# Hi_Tension_VGA_Modulator.net
KiCad netlist of a schematic drawn in EAGLE
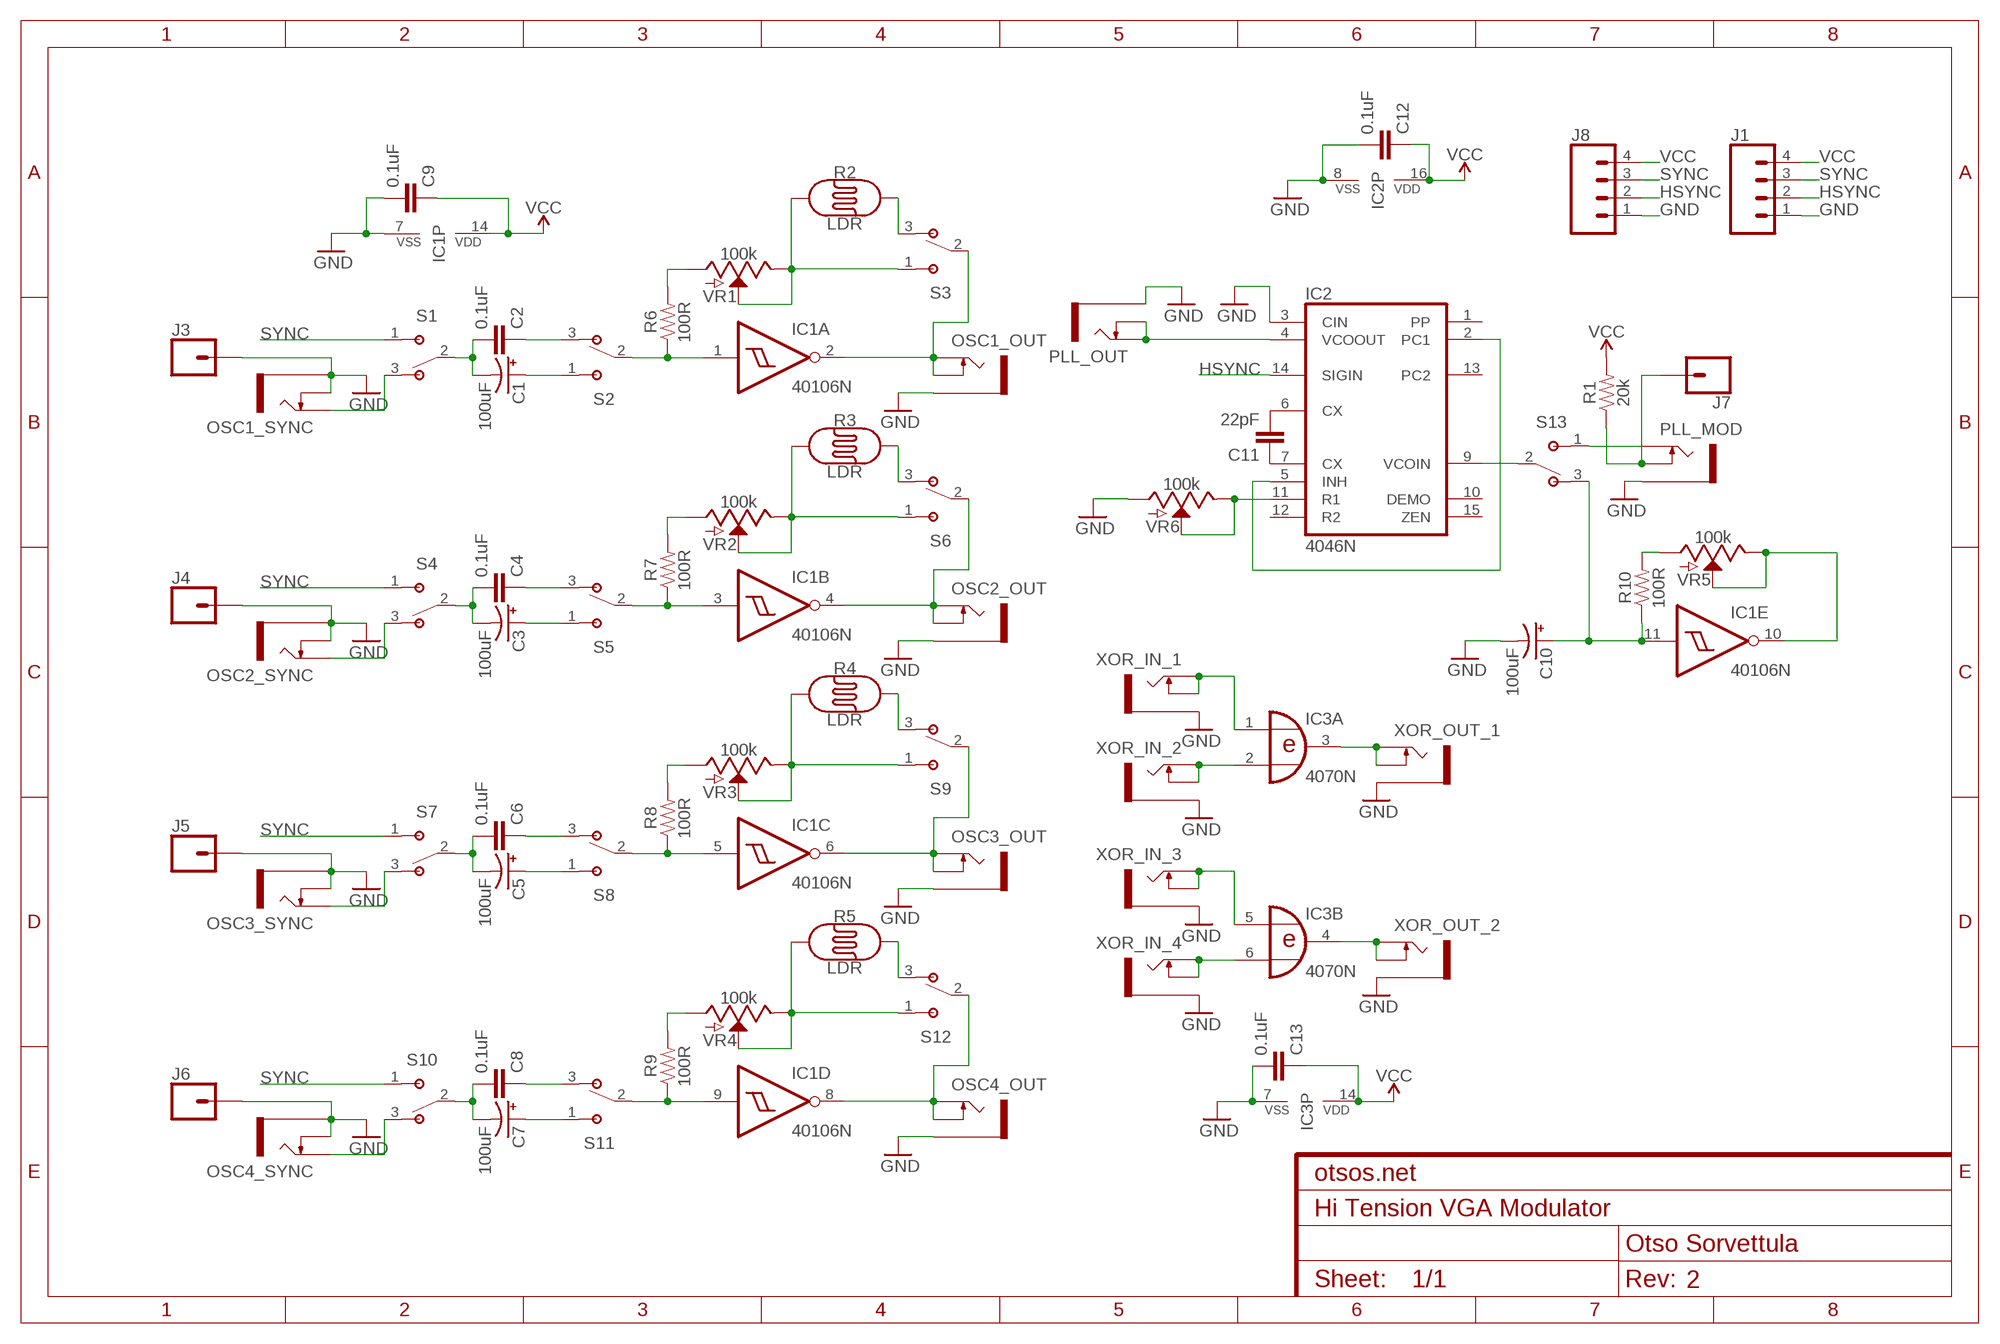
[diagram p0: schematic, sheet 1]

(export (version "E")
  (design (tool "Eeschema 10.0.6"))
  (components
    (comp (ref "C1")
      (value "100uF")
      (footprint "eagle-import:CPOL-RADIAL-2.5MM-6.5MM")
      (libsource (lib "eagle-import") (part "100UF-POLAR-RADIAL-2.5MM-25V-20%"))
    )
    (comp (ref "C2")
      (value "0.1uF")
      (footprint "eagle-import:C025-025X050")
      (libsource (lib "eagle-import") (part "C-EU025-025X050"))
    )
    (comp (ref "C3")
      (value "100uF")
      (footprint "eagle-import:CPOL-RADIAL-2.5MM-6.5MM")
      (libsource (lib "eagle-import") (part "100UF-POLAR-RADIAL-2.5MM-25V-20%"))
    )
    (comp (ref "C4")
      (value "0.1uF")
      (footprint "eagle-import:C025-025X050")
      (libsource (lib "eagle-import") (part "C-EU025-025X050"))
    )
    (comp (ref "C5")
      (value "100uF")
      (footprint "eagle-import:CPOL-RADIAL-2.5MM-6.5MM")
      (libsource (lib "eagle-import") (part "100UF-POLAR-RADIAL-2.5MM-25V-20%"))
    )
    (comp (ref "C6")
      (value "0.1uF")
      (footprint "eagle-import:C025-025X050")
      (libsource (lib "eagle-import") (part "C-EU025-025X050"))
    )
    (comp (ref "C7")
      (value "100uF")
      (footprint "eagle-import:CPOL-RADIAL-2.5MM-6.5MM")
      (libsource (lib "eagle-import") (part "100UF-POLAR-RADIAL-2.5MM-25V-20%"))
    )
    (comp (ref "C8")
      (value "0.1uF")
      (footprint "eagle-import:C025-025X050")
      (libsource (lib "eagle-import") (part "C-EU025-025X050"))
    )
    (comp (ref "C9")
      (value "0.1uF")
      (footprint "eagle-import:C025-025X050")
      (libsource (lib "eagle-import") (part "C-EU025-025X050"))
    )
    (comp (ref "C10")
      (value "100uF")
      (footprint "eagle-import:CPOL-RADIAL-2.5MM-6.5MM")
      (libsource (lib "eagle-import") (part "100UF-POLAR-RADIAL-2.5MM-25V-20%"))
    )
    (comp (ref "C11")
      (value "22pF")
      (footprint "eagle-import:CAP-PTH-2.54")
      (libsource (lib "eagle-import") (part "22PF-PTH-2.54MM-200V-5%"))
    )
    (comp (ref "C12")
      (value "0.1uF")
      (footprint "eagle-import:C025-025X050")
      (libsource (lib "eagle-import") (part "C-EU025-025X050"))
    )
    (comp (ref "C13")
      (value "0.1uF")
      (footprint "eagle-import:C025-025X050")
      (libsource (lib "eagle-import") (part "C-EU025-025X050"))
    )
    (comp (ref "IC1")
      (value "40106N")
      (footprint "eagle-import:DIL14")
      (libsource (lib "eagle-import") (part "40106N"))
    )
    (comp (ref "IC2")
      (value "4046N")
      (footprint "eagle-import:DIL16")
      (libsource (lib "eagle-import") (part "4046N"))
    )
    (comp (ref "IC3")
      (value "4070N")
      (footprint "eagle-import:DIL14")
      (libsource (lib "eagle-import") (part "4070N"))
    )
    (comp (ref "J1")
      (value "CONN_04")
      (footprint "eagle-import:1X04")
      (libsource (lib "eagle-import") (part "CONN_04"))
    )
    (comp (ref "J3")
      (value "CONN_01PTH_NO_SILK_YES_STOP")
      (footprint "eagle-import:1X01_NO_SILK")
      (libsource (lib "eagle-import") (part "CONN_01PTH_NO_SILK_YES_STOP"))
    )
    (comp (ref "J4")
      (value "CONN_01PTH_NO_SILK_YES_STOP")
      (footprint "eagle-import:1X01_NO_SILK")
      (libsource (lib "eagle-import") (part "CONN_01PTH_NO_SILK_YES_STOP"))
    )
    (comp (ref "J5")
      (value "CONN_01PTH_NO_SILK_YES_STOP")
      (footprint "eagle-import:1X01_NO_SILK")
      (libsource (lib "eagle-import") (part "CONN_01PTH_NO_SILK_YES_STOP"))
    )
    (comp (ref "J6")
      (value "CONN_01PTH_NO_SILK_YES_STOP")
      (footprint "eagle-import:1X01_NO_SILK")
      (libsource (lib "eagle-import") (part "CONN_01PTH_NO_SILK_YES_STOP"))
    )
    (comp (ref "J7")
      (value "CONN_01PTH_NO_SILK_YES_STOP")
      (footprint "eagle-import:1X01_NO_SILK")
      (libsource (lib "eagle-import") (part "CONN_01PTH_NO_SILK_YES_STOP"))
    )
    (comp (ref "J8")
      (value "CONN_04")
      (footprint "eagle-import:1X04")
      (libsource (lib "eagle-import") (part "CONN_04"))
    )
    (comp (ref "OSC1_OUT")
      (value "THONKICONNNEW")
      (footprint "eagle-import:WQP-PJ301M-12_JACK")
      (libsource (lib "eagle-import") (part "THONKICONNNEW"))
    )
    (comp (ref "OSC1_SYNC")
      (value "THONKICONNNEW")
      (footprint "eagle-import:WQP-PJ301M-12_JACK")
      (libsource (lib "eagle-import") (part "THONKICONNNEW"))
    )
    (comp (ref "OSC2_OUT")
      (value "THONKICONNNEW")
      (footprint "eagle-import:WQP-PJ301M-12_JACK")
      (libsource (lib "eagle-import") (part "THONKICONNNEW"))
    )
    (comp (ref "OSC2_SYNC")
      (value "THONKICONNNEW")
      (footprint "eagle-import:WQP-PJ301M-12_JACK")
      (libsource (lib "eagle-import") (part "THONKICONNNEW"))
    )
    (comp (ref "OSC3_OUT")
      (value "THONKICONNNEW")
      (footprint "eagle-import:WQP-PJ301M-12_JACK")
      (libsource (lib "eagle-import") (part "THONKICONNNEW"))
    )
    (comp (ref "OSC3_SYNC")
      (value "THONKICONNNEW")
      (footprint "eagle-import:WQP-PJ301M-12_JACK")
      (libsource (lib "eagle-import") (part "THONKICONNNEW"))
    )
    (comp (ref "OSC4_OUT")
      (value "THONKICONNNEW")
      (footprint "eagle-import:WQP-PJ301M-12_JACK")
      (libsource (lib "eagle-import") (part "THONKICONNNEW"))
    )
    (comp (ref "OSC4_SYNC")
      (value "THONKICONNNEW")
      (footprint "eagle-import:WQP-PJ301M-12_JACK")
      (libsource (lib "eagle-import") (part "THONKICONNNEW"))
    )
    (comp (ref "PLL_MOD")
      (value "THONKICONNNEW")
      (footprint "eagle-import:WQP-PJ301M-12_JACK")
      (libsource (lib "eagle-import") (part "THONKICONNNEW"))
    )
    (comp (ref "PLL_OUT")
      (value "THONKICONNNEW")
      (footprint "eagle-import:WQP-PJ301M-12_JACK")
      (libsource (lib "eagle-import") (part "THONKICONNNEW"))
    )
    (comp (ref "R1")
      (value "20k")
      (footprint "eagle-import:AXIAL-0.3")
      (libsource (lib "eagle-import") (part "1KOHM-HORIZ-1/4W-1%"))
    )
    (comp (ref "R2")
      (value "LDR")
      (footprint "eagle-import:PHOTOCELL")
      (libsource (lib "eagle-import") (part "PHOTOCELLPTH"))
    )
    (comp (ref "R3")
      (value "LDR")
      (footprint "eagle-import:PHOTOCELL")
      (libsource (lib "eagle-import") (part "PHOTOCELLPTH"))
    )
    (comp (ref "R4")
      (value "LDR")
      (footprint "eagle-import:PHOTOCELL")
      (libsource (lib "eagle-import") (part "PHOTOCELLPTH"))
    )
    (comp (ref "R5")
      (value "LDR")
      (footprint "eagle-import:PHOTOCELL")
      (libsource (lib "eagle-import") (part "PHOTOCELLPTH"))
    )
    (comp (ref "R6")
      (value "100R")
      (footprint "eagle-import:AXIAL-0.3")
      (libsource (lib "eagle-import") (part "1KOHM-HORIZ-1/4W-1%"))
    )
    (comp (ref "R7")
      (value "100R")
      (footprint "eagle-import:AXIAL-0.3")
      (libsource (lib "eagle-import") (part "1KOHM-HORIZ-1/4W-1%"))
    )
    (comp (ref "R8")
      (value "100R")
      (footprint "eagle-import:AXIAL-0.3")
      (libsource (lib "eagle-import") (part "1KOHM-HORIZ-1/4W-1%"))
    )
    (comp (ref "R9")
      (value "100R")
      (footprint "eagle-import:AXIAL-0.3")
      (libsource (lib "eagle-import") (part "1KOHM-HORIZ-1/4W-1%"))
    )
    (comp (ref "R10")
      (value "100R")
      (footprint "eagle-import:AXIAL-0.3")
      (libsource (lib "eagle-import") (part "1KOHM-HORIZ-1/4W-1%"))
    )
    (comp (ref "S1")
      (value "OS102011MS2QN1")
      (footprint "eagle-import:SW_OS102011MS2QN1")
      (fields (field (name "MF") "C&K"))
      (libsource (lib "eagle-import") (part "OS102011MS2QN1"))
    )
    (comp (ref "S2")
      (value "OS102011MS2QN1")
      (footprint "eagle-import:SW_OS102011MS2QN1")
      (fields (field (name "MF") "C&K"))
      (libsource (lib "eagle-import") (part "OS102011MS2QN1"))
    )
    (comp (ref "S3")
      (value "OS102011MS2QN1")
      (footprint "eagle-import:SW_OS102011MS2QN1")
      (fields (field (name "MF") "C&K"))
      (libsource (lib "eagle-import") (part "OS102011MS2QN1"))
    )
    (comp (ref "S4")
      (value "OS102011MS2QN1")
      (footprint "eagle-import:SW_OS102011MS2QN1")
      (fields (field (name "MF") "C&K"))
      (libsource (lib "eagle-import") (part "OS102011MS2QN1"))
    )
    (comp (ref "S5")
      (value "OS102011MS2QN1")
      (footprint "eagle-import:SW_OS102011MS2QN1")
      (fields (field (name "MF") "C&K"))
      (libsource (lib "eagle-import") (part "OS102011MS2QN1"))
    )
    (comp (ref "S6")
      (value "OS102011MS2QN1")
      (footprint "eagle-import:SW_OS102011MS2QN1")
      (fields (field (name "MF") "C&K"))
      (libsource (lib "eagle-import") (part "OS102011MS2QN1"))
    )
    (comp (ref "S7")
      (value "OS102011MS2QN1")
      (footprint "eagle-import:SW_OS102011MS2QN1")
      (fields (field (name "MF") "C&K"))
      (libsource (lib "eagle-import") (part "OS102011MS2QN1"))
    )
    (comp (ref "S8")
      (value "OS102011MS2QN1")
      (footprint "eagle-import:SW_OS102011MS2QN1")
      (fields (field (name "MF") "C&K"))
      (libsource (lib "eagle-import") (part "OS102011MS2QN1"))
    )
    (comp (ref "S9")
      (value "OS102011MS2QN1")
      (footprint "eagle-import:SW_OS102011MS2QN1")
      (fields (field (name "MF") "C&K"))
      (libsource (lib "eagle-import") (part "OS102011MS2QN1"))
    )
    (comp (ref "S10")
      (value "OS102011MS2QN1")
      (footprint "eagle-import:SW_OS102011MS2QN1")
      (fields (field (name "MF") "C&K"))
      (libsource (lib "eagle-import") (part "OS102011MS2QN1"))
    )
    (comp (ref "S11")
      (value "OS102011MS2QN1")
      (footprint "eagle-import:SW_OS102011MS2QN1")
      (fields (field (name "MF") "C&K"))
      (libsource (lib "eagle-import") (part "OS102011MS2QN1"))
    )
    (comp (ref "S12")
      (value "OS102011MS2QN1")
      (footprint "eagle-import:SW_OS102011MS2QN1")
      (fields (field (name "MF") "C&K"))
      (libsource (lib "eagle-import") (part "OS102011MS2QN1"))
    )
    (comp (ref "S13")
      (value "OS102011MS2QN1")
      (footprint "eagle-import:SW_OS102011MS2QN1")
      (fields (field (name "MF") "C&K"))
      (libsource (lib "eagle-import") (part "OS102011MS2QN1"))
    )
    (comp (ref "VR1")
      (value "100k")
      (footprint "eagle-import:POT-PTH-ALPS")
      (libsource (lib "eagle-import") (part "POTENTIOMETER-PTH-9MM-1/20W-20%"))
    )
    (comp (ref "VR2")
      (value "100k")
      (footprint "eagle-import:POT-PTH-ALPS")
      (libsource (lib "eagle-import") (part "POTENTIOMETER-PTH-9MM-1/20W-20%"))
    )
    (comp (ref "VR3")
      (value "100k")
      (footprint "eagle-import:POT-PTH-ALPS")
      (libsource (lib "eagle-import") (part "POTENTIOMETER-PTH-9MM-1/20W-20%"))
    )
    (comp (ref "VR4")
      (value "100k")
      (footprint "eagle-import:POT-PTH-ALPS")
      (libsource (lib "eagle-import") (part "POTENTIOMETER-PTH-9MM-1/20W-20%"))
    )
    (comp (ref "VR5")
      (value "100k")
      (footprint "eagle-import:POT-PTH-ALPS")
      (libsource (lib "eagle-import") (part "POTENTIOMETER-PTH-9MM-1/20W-20%"))
    )
    (comp (ref "VR6")
      (value "100k")
      (footprint "eagle-import:POT-PTH-ALPS")
      (libsource (lib "eagle-import") (part "POTENTIOMETER-PTH-9MM-1/20W-20%"))
    )
    (comp (ref "XOR_IN_1")
      (value "THONKICONNNEW")
      (footprint "eagle-import:WQP-PJ301M-12_JACK")
      (libsource (lib "eagle-import") (part "THONKICONNNEW"))
    )
    (comp (ref "XOR_IN_2")
      (value "THONKICONNNEW")
      (footprint "eagle-import:WQP-PJ301M-12_JACK")
      (libsource (lib "eagle-import") (part "THONKICONNNEW"))
    )
    (comp (ref "XOR_IN_3")
      (value "THONKICONNNEW")
      (footprint "eagle-import:WQP-PJ301M-12_JACK")
      (libsource (lib "eagle-import") (part "THONKICONNNEW"))
    )
    (comp (ref "XOR_IN_4")
      (value "THONKICONNNEW")
      (footprint "eagle-import:WQP-PJ301M-12_JACK")
      (libsource (lib "eagle-import") (part "THONKICONNNEW"))
    )
    (comp (ref "XOR_OUT_1")
      (value "THONKICONNNEW")
      (footprint "eagle-import:WQP-PJ301M-12_JACK")
      (libsource (lib "eagle-import") (part "THONKICONNNEW"))
    )
    (comp (ref "XOR_OUT_2")
      (value "THONKICONNNEW")
      (footprint "eagle-import:WQP-PJ301M-12_JACK")
      (libsource (lib "eagle-import") (part "THONKICONNNEW"))
    )
  )
  (nets
    (net (code "1") (name "/HSYNC") (class "Default")
      (node (ref "IC2") (pin "14") (pinfunction "SIGIN_14") (pintype "input"))
      (node (ref "J1") (pin "2") (pinfunction "2_2") (pintype "passive"))
      (node (ref "J8") (pin "2") (pinfunction "2_2") (pintype "passive"))
    )
    (net (code "2") (name "/SYNC") (class "Default")
      (node (ref "J1") (pin "3") (pinfunction "3_3") (pintype "passive"))
      (node (ref "J8") (pin "3") (pinfunction "3_3") (pintype "passive"))
      (node (ref "S1") (pin "1") (pinfunction "1_1") (pintype "passive"))
      (node (ref "S10") (pin "1") (pinfunction "1_1") (pintype "passive"))
      (node (ref "S4") (pin "1") (pinfunction "1_1") (pintype "passive"))
      (node (ref "S7") (pin "1") (pinfunction "1_1") (pintype "passive"))
    )
    (net (code "3") (name "GND") (class "Default")
      (node (ref "C10") (pin "2") (pinfunction "-_2") (pintype "passive"))
      (node (ref "C12") (pin "2") (pinfunction "2_2") (pintype "passive"))
      (node (ref "C13") (pin "2") (pinfunction "2_2") (pintype "passive"))
      (node (ref "C9") (pin "2") (pinfunction "2_2") (pintype "passive"))
      (node (ref "IC1") (pin "7") (pinfunction "VSS_7") (pintype "power_in"))
      (node (ref "IC2") (pin "3") (pinfunction "CIN_3") (pintype "input"))
      (node (ref "IC2") (pin "8") (pinfunction "VSS_8") (pintype "power_in"))
      (node (ref "IC3") (pin "7") (pinfunction "VSS_7") (pintype "power_in"))
      (node (ref "J1") (pin "1") (pinfunction "1_1") (pintype "passive"))
      (node (ref "J3") (pin "1") (pinfunction "1_1") (pintype "passive"))
      (node (ref "J4") (pin "1") (pinfunction "1_1") (pintype "passive"))
      (node (ref "J5") (pin "1") (pinfunction "1_1") (pintype "passive"))
      (node (ref "J6") (pin "1") (pinfunction "1_1") (pintype "passive"))
      (node (ref "J8") (pin "1") (pinfunction "1_1") (pintype "passive"))
      (node (ref "OSC1_OUT") (pin "P$3_SLEEVE") (pinfunction "SLEEVE_P$3_SLEEVE") (pintype "passive"))
      (node (ref "OSC1_SYNC") (pin "P$2_SWITCH") (pinfunction "SWITCH_P$2_SWITCH") (pintype "passive"))
      (node (ref "OSC1_SYNC") (pin "P$3_SLEEVE") (pinfunction "SLEEVE_P$3_SLEEVE") (pintype "passive"))
      (node (ref "OSC2_OUT") (pin "P$3_SLEEVE") (pinfunction "SLEEVE_P$3_SLEEVE") (pintype "passive"))
      (node (ref "OSC2_SYNC") (pin "P$2_SWITCH") (pinfunction "SWITCH_P$2_SWITCH") (pintype "passive"))
      (node (ref "OSC2_SYNC") (pin "P$3_SLEEVE") (pinfunction "SLEEVE_P$3_SLEEVE") (pintype "passive"))
      (node (ref "OSC3_OUT") (pin "P$3_SLEEVE") (pinfunction "SLEEVE_P$3_SLEEVE") (pintype "passive"))
      (node (ref "OSC3_SYNC") (pin "P$2_SWITCH") (pinfunction "SWITCH_P$2_SWITCH") (pintype "passive"))
      (node (ref "OSC3_SYNC") (pin "P$3_SLEEVE") (pinfunction "SLEEVE_P$3_SLEEVE") (pintype "passive"))
      (node (ref "OSC4_OUT") (pin "P$3_SLEEVE") (pinfunction "SLEEVE_P$3_SLEEVE") (pintype "passive"))
      (node (ref "OSC4_SYNC") (pin "P$2_SWITCH") (pinfunction "SWITCH_P$2_SWITCH") (pintype "passive"))
      (node (ref "OSC4_SYNC") (pin "P$3_SLEEVE") (pinfunction "SLEEVE_P$3_SLEEVE") (pintype "passive"))
      (node (ref "PLL_MOD") (pin "P$3_SLEEVE") (pinfunction "SLEEVE_P$3_SLEEVE") (pintype "passive"))
      (node (ref "PLL_OUT") (pin "P$3_SLEEVE") (pinfunction "SLEEVE_P$3_SLEEVE") (pintype "passive"))
      (node (ref "VR6") (pin "P$3") (pinfunction "A_P$3") (pintype "passive"))
      (node (ref "XOR_IN_1") (pin "P$3_SLEEVE") (pinfunction "SLEEVE_P$3_SLEEVE") (pintype "passive"))
      (node (ref "XOR_IN_2") (pin "P$3_SLEEVE") (pinfunction "SLEEVE_P$3_SLEEVE") (pintype "passive"))
      (node (ref "XOR_IN_3") (pin "P$3_SLEEVE") (pinfunction "SLEEVE_P$3_SLEEVE") (pintype "passive"))
      (node (ref "XOR_IN_4") (pin "P$3_SLEEVE") (pinfunction "SLEEVE_P$3_SLEEVE") (pintype "passive"))
      (node (ref "XOR_OUT_1") (pin "P$3_SLEEVE") (pinfunction "SLEEVE_P$3_SLEEVE") (pintype "passive"))
      (node (ref "XOR_OUT_2") (pin "P$3_SLEEVE") (pinfunction "SLEEVE_P$3_SLEEVE") (pintype "passive"))
    )
    (net (code "4") (name "Net-(C1-+)") (class "Default")
      (node (ref "C1") (pin "1") (pinfunction "+_1") (pintype "passive"))
      (node (ref "S2") (pin "1") (pinfunction "1_1") (pintype "passive"))
    )
    (net (code "5") (name "Net-(C1--)") (class "Default")
      (node (ref "C1") (pin "2") (pinfunction "-_2") (pintype "passive"))
      (node (ref "C2") (pin "2") (pinfunction "2_2") (pintype "passive"))
      (node (ref "S1") (pin "2") (pinfunction "2_2") (pintype "passive"))
    )
    (net (code "6") (name "Net-(C2-Pad1)") (class "Default")
      (node (ref "C2") (pin "1") (pinfunction "1_1") (pintype "passive"))
      (node (ref "S2") (pin "3") (pinfunction "3_3") (pintype "passive"))
    )
    (net (code "7") (name "Net-(C3-+)") (class "Default")
      (node (ref "C3") (pin "1") (pinfunction "+_1") (pintype "passive"))
      (node (ref "S5") (pin "1") (pinfunction "1_1") (pintype "passive"))
    )
    (net (code "8") (name "Net-(C3--)") (class "Default")
      (node (ref "C3") (pin "2") (pinfunction "-_2") (pintype "passive"))
      (node (ref "C4") (pin "2") (pinfunction "2_2") (pintype "passive"))
      (node (ref "S4") (pin "2") (pinfunction "2_2") (pintype "passive"))
    )
    (net (code "9") (name "Net-(C4-Pad1)") (class "Default")
      (node (ref "C4") (pin "1") (pinfunction "1_1") (pintype "passive"))
      (node (ref "S5") (pin "3") (pinfunction "3_3") (pintype "passive"))
    )
    (net (code "10") (name "Net-(C5-+)") (class "Default")
      (node (ref "C5") (pin "1") (pinfunction "+_1") (pintype "passive"))
      (node (ref "S8") (pin "1") (pinfunction "1_1") (pintype "passive"))
    )
    (net (code "11") (name "Net-(C5--)") (class "Default")
      (node (ref "C5") (pin "2") (pinfunction "-_2") (pintype "passive"))
      (node (ref "C6") (pin "2") (pinfunction "2_2") (pintype "passive"))
      (node (ref "S7") (pin "2") (pinfunction "2_2") (pintype "passive"))
    )
    (net (code "12") (name "Net-(C6-Pad1)") (class "Default")
      (node (ref "C6") (pin "1") (pinfunction "1_1") (pintype "passive"))
      (node (ref "S8") (pin "3") (pinfunction "3_3") (pintype "passive"))
    )
    (net (code "13") (name "Net-(C7-+)") (class "Default")
      (node (ref "C7") (pin "1") (pinfunction "+_1") (pintype "passive"))
      (node (ref "S11") (pin "1") (pinfunction "1_1") (pintype "passive"))
    )
    (net (code "14") (name "Net-(C7--)") (class "Default")
      (node (ref "C7") (pin "2") (pinfunction "-_2") (pintype "passive"))
      (node (ref "C8") (pin "2") (pinfunction "2_2") (pintype "passive"))
      (node (ref "S10") (pin "2") (pinfunction "2_2") (pintype "passive"))
    )
    (net (code "15") (name "Net-(C8-Pad1)") (class "Default")
      (node (ref "C8") (pin "1") (pinfunction "1_1") (pintype "passive"))
      (node (ref "S11") (pin "3") (pinfunction "3_3") (pintype "passive"))
    )
    (net (code "16") (name "Net-(C10-+)") (class "Default")
      (node (ref "C10") (pin "1") (pinfunction "+_1") (pintype "passive"))
      (node (ref "IC1") (pin "11") (pinfunction "I_11") (pintype "input"))
      (node (ref "R10") (pin "P$1") (pinfunction "1_P$1") (pintype "passive"))
      (node (ref "S13") (pin "3") (pinfunction "3_3") (pintype "passive"))
    )
    (net (code "17") (name "Net-(C11-Pad1)") (class "Default")
      (node (ref "C11") (pin "1") (pinfunction "1_1") (pintype "passive"))
      (node (ref "IC2") (pin "7") (pinfunction "CX_7") (pintype "input"))
    )
    (net (code "18") (name "Net-(C11-Pad2)") (class "Default")
      (node (ref "C11") (pin "2") (pinfunction "2_2") (pintype "passive"))
      (node (ref "IC2") (pin "6") (pinfunction "CX_6") (pintype "input"))
    )
    (net (code "19") (name "Net-(IC1A-I)") (class "Default")
      (node (ref "IC1") (pin "1") (pinfunction "I_1") (pintype "input"))
      (node (ref "R6") (pin "P$1") (pinfunction "1_P$1") (pintype "passive"))
      (node (ref "S2") (pin "2") (pinfunction "2_2") (pintype "passive"))
    )
    (net (code "20") (name "Net-(IC1A-O)") (class "Default")
      (node (ref "IC1") (pin "2") (pinfunction "O_2") (pintype "output"))
      (node (ref "OSC1_OUT") (pin "P$1_TIP") (pinfunction "TIP_P$1_TIP") (pintype "passive"))
      (node (ref "OSC1_OUT") (pin "P$2_SWITCH") (pinfunction "SWITCH_P$2_SWITCH") (pintype "passive"))
      (node (ref "S3") (pin "2") (pinfunction "2_2") (pintype "passive"))
    )
    (net (code "21") (name "Net-(IC1B-I)") (class "Default")
      (node (ref "IC1") (pin "3") (pinfunction "I_3") (pintype "input"))
      (node (ref "R7") (pin "P$1") (pinfunction "1_P$1") (pintype "passive"))
      (node (ref "S5") (pin "2") (pinfunction "2_2") (pintype "passive"))
    )
    (net (code "22") (name "Net-(IC1B-O)") (class "Default")
      (node (ref "IC1") (pin "4") (pinfunction "O_4") (pintype "output"))
      (node (ref "OSC2_OUT") (pin "P$1_TIP") (pinfunction "TIP_P$1_TIP") (pintype "passive"))
      (node (ref "OSC2_OUT") (pin "P$2_SWITCH") (pinfunction "SWITCH_P$2_SWITCH") (pintype "passive"))
      (node (ref "S6") (pin "2") (pinfunction "2_2") (pintype "passive"))
    )
    (net (code "23") (name "Net-(IC1C-I)") (class "Default")
      (node (ref "IC1") (pin "5") (pinfunction "I_5") (pintype "input"))
      (node (ref "R8") (pin "P$1") (pinfunction "1_P$1") (pintype "passive"))
      (node (ref "S8") (pin "2") (pinfunction "2_2") (pintype "passive"))
    )
    (net (code "24") (name "Net-(IC1C-O)") (class "Default")
      (node (ref "IC1") (pin "6") (pinfunction "O_6") (pintype "output"))
      (node (ref "OSC3_OUT") (pin "P$1_TIP") (pinfunction "TIP_P$1_TIP") (pintype "passive"))
      (node (ref "OSC3_OUT") (pin "P$2_SWITCH") (pinfunction "SWITCH_P$2_SWITCH") (pintype "passive"))
      (node (ref "S9") (pin "2") (pinfunction "2_2") (pintype "passive"))
    )
    (net (code "25") (name "Net-(IC1D-I)") (class "Default")
      (node (ref "IC1") (pin "9") (pinfunction "I_9") (pintype "input"))
      (node (ref "R9") (pin "P$1") (pinfunction "1_P$1") (pintype "passive"))
      (node (ref "S11") (pin "2") (pinfunction "2_2") (pintype "passive"))
    )
    (net (code "26") (name "Net-(IC1D-O)") (class "Default")
      (node (ref "IC1") (pin "8") (pinfunction "O_8") (pintype "output"))
      (node (ref "OSC4_OUT") (pin "P$1_TIP") (pinfunction "TIP_P$1_TIP") (pintype "passive"))
      (node (ref "OSC4_OUT") (pin "P$2_SWITCH") (pinfunction "SWITCH_P$2_SWITCH") (pintype "passive"))
      (node (ref "S12") (pin "2") (pinfunction "2_2") (pintype "passive"))
    )
    (net (code "27") (name "Net-(IC1E-O)") (class "Default")
      (node (ref "IC1") (pin "10") (pinfunction "O_10") (pintype "output"))
      (node (ref "VR5") (pin "P$1") (pinfunction "E_P$1") (pintype "passive"))
      (node (ref "VR5") (pin "P$2") (pinfunction "S_P$2") (pintype "passive"))
    )
    (net (code "28") (name "Net-(IC2A-INH)") (class "Default")
      (node (ref "IC2") (pin "2") (pinfunction "PC1_2") (pintype "output"))
      (node (ref "IC2") (pin "5") (pinfunction "INH_5") (pintype "input"))
    )
    (net (code "29") (name "Net-(IC2A-R1)") (class "Default")
      (node (ref "IC2") (pin "11") (pinfunction "R1_11") (pintype "input"))
      (node (ref "VR6") (pin "P$1") (pinfunction "E_P$1") (pintype "passive"))
      (node (ref "VR6") (pin "P$2") (pinfunction "S_P$2") (pintype "passive"))
    )
    (net (code "30") (name "Net-(IC2A-VCOIN)") (class "Default")
      (node (ref "IC2") (pin "9") (pinfunction "VCOIN_9") (pintype "input"))
      (node (ref "S13") (pin "2") (pinfunction "2_2") (pintype "passive"))
    )
    (net (code "31") (name "Net-(IC2A-VCOOUT)") (class "Default")
      (node (ref "IC2") (pin "4") (pinfunction "VCOOUT_4") (pintype "output"))
      (node (ref "PLL_OUT") (pin "P$1_TIP") (pinfunction "TIP_P$1_TIP") (pintype "passive"))
      (node (ref "PLL_OUT") (pin "P$2_SWITCH") (pinfunction "SWITCH_P$2_SWITCH") (pintype "passive"))
    )
    (net (code "32") (name "Net-(IC3A-I0)") (class "Default")
      (node (ref "IC3") (pin "1") (pinfunction "I0_1") (pintype "input"))
      (node (ref "XOR_IN_1") (pin "P$1_TIP") (pinfunction "TIP_P$1_TIP") (pintype "passive"))
      (node (ref "XOR_IN_1") (pin "P$2_SWITCH") (pinfunction "SWITCH_P$2_SWITCH") (pintype "passive"))
    )
    (net (code "33") (name "Net-(IC3A-I1)") (class "Default")
      (node (ref "IC3") (pin "2") (pinfunction "I1_2") (pintype "input"))
      (node (ref "XOR_IN_2") (pin "P$1_TIP") (pinfunction "TIP_P$1_TIP") (pintype "passive"))
      (node (ref "XOR_IN_2") (pin "P$2_SWITCH") (pinfunction "SWITCH_P$2_SWITCH") (pintype "passive"))
    )
    (net (code "34") (name "Net-(IC3A-O)") (class "Default")
      (node (ref "IC3") (pin "3") (pinfunction "O_3") (pintype "output"))
      (node (ref "XOR_OUT_1") (pin "P$1_TIP") (pinfunction "TIP_P$1_TIP") (pintype "passive"))
      (node (ref "XOR_OUT_1") (pin "P$2_SWITCH") (pinfunction "SWITCH_P$2_SWITCH") (pintype "passive"))
    )
    (net (code "35") (name "Net-(IC3B-I0)") (class "Default")
      (node (ref "IC3") (pin "5") (pinfunction "I0_5") (pintype "input"))
      (node (ref "XOR_IN_3") (pin "P$1_TIP") (pinfunction "TIP_P$1_TIP") (pintype "passive"))
      (node (ref "XOR_IN_3") (pin "P$2_SWITCH") (pinfunction "SWITCH_P$2_SWITCH") (pintype "passive"))
    )
    (net (code "36") (name "Net-(IC3B-I1)") (class "Default")
      (node (ref "IC3") (pin "6") (pinfunction "I1_6") (pintype "input"))
      (node (ref "XOR_IN_4") (pin "P$1_TIP") (pinfunction "TIP_P$1_TIP") (pintype "passive"))
      (node (ref "XOR_IN_4") (pin "P$2_SWITCH") (pinfunction "SWITCH_P$2_SWITCH") (pintype "passive"))
    )
    (net (code "37") (name "Net-(IC3B-O)") (class "Default")
      (node (ref "IC3") (pin "4") (pinfunction "O_4") (pintype "output"))
      (node (ref "XOR_OUT_2") (pin "P$1_TIP") (pinfunction "TIP_P$1_TIP") (pintype "passive"))
      (node (ref "XOR_OUT_2") (pin "P$2_SWITCH") (pinfunction "SWITCH_P$2_SWITCH") (pintype "passive"))
    )
    (net (code "38") (name "Net-(OSC1_SYNC-TIP)") (class "Default")
      (node (ref "OSC1_SYNC") (pin "P$1_TIP") (pinfunction "TIP_P$1_TIP") (pintype "passive"))
      (node (ref "S1") (pin "3") (pinfunction "3_3") (pintype "passive"))
    )
    (net (code "39") (name "Net-(OSC2_SYNC-TIP)") (class "Default")
      (node (ref "OSC2_SYNC") (pin "P$1_TIP") (pinfunction "TIP_P$1_TIP") (pintype "passive"))
      (node (ref "S4") (pin "3") (pinfunction "3_3") (pintype "passive"))
    )
    (net (code "40") (name "Net-(OSC3_SYNC-TIP)") (class "Default")
      (node (ref "OSC3_SYNC") (pin "P$1_TIP") (pinfunction "TIP_P$1_TIP") (pintype "passive"))
      (node (ref "S7") (pin "3") (pinfunction "3_3") (pintype "passive"))
    )
    (net (code "41") (name "Net-(OSC4_SYNC-TIP)") (class "Default")
      (node (ref "OSC4_SYNC") (pin "P$1_TIP") (pinfunction "TIP_P$1_TIP") (pintype "passive"))
      (node (ref "S10") (pin "3") (pinfunction "3_3") (pintype "passive"))
    )
    (net (code "42") (name "Net-(PLL_MOD-SWITCH)") (class "Default")
      (node (ref "J7") (pin "1") (pinfunction "1_1") (pintype "passive"))
      (node (ref "PLL_MOD") (pin "P$2_SWITCH") (pinfunction "SWITCH_P$2_SWITCH") (pintype "passive"))
      (node (ref "R1") (pin "P$1") (pinfunction "1_P$1") (pintype "passive"))
    )
    (net (code "43") (name "Net-(PLL_MOD-TIP)") (class "Default")
      (node (ref "PLL_MOD") (pin "P$1_TIP") (pinfunction "TIP_P$1_TIP") (pintype "passive"))
      (node (ref "S13") (pin "1") (pinfunction "1_1") (pintype "passive"))
    )
    (net (code "44") (name "Net-(R2-P$1)") (class "Default")
      (node (ref "R2") (pin "1") (pinfunction "P$1_1") (pintype "bidirectional"))
      (node (ref "S3") (pin "1") (pinfunction "1_1") (pintype "passive"))
      (node (ref "VR1") (pin "P$1") (pinfunction "E_P$1") (pintype "passive"))
      (node (ref "VR1") (pin "P$2") (pinfunction "S_P$2") (pintype "passive"))
    )
    (net (code "45") (name "Net-(R2-P$2)") (class "Default")
      (node (ref "R2") (pin "2") (pinfunction "P$2_2") (pintype "bidirectional"))
      (node (ref "S3") (pin "3") (pinfunction "3_3") (pintype "passive"))
    )
    (net (code "46") (name "Net-(R3-P$1)") (class "Default")
      (node (ref "R3") (pin "1") (pinfunction "P$1_1") (pintype "bidirectional"))
      (node (ref "S6") (pin "1") (pinfunction "1_1") (pintype "passive"))
      (node (ref "VR2") (pin "P$1") (pinfunction "E_P$1") (pintype "passive"))
      (node (ref "VR2") (pin "P$2") (pinfunction "S_P$2") (pintype "passive"))
    )
    (net (code "47") (name "Net-(R3-P$2)") (class "Default")
      (node (ref "R3") (pin "2") (pinfunction "P$2_2") (pintype "bidirectional"))
      (node (ref "S6") (pin "3") (pinfunction "3_3") (pintype "passive"))
    )
    (net (code "48") (name "Net-(R4-P$1)") (class "Default")
      (node (ref "R4") (pin "1") (pinfunction "P$1_1") (pintype "bidirectional"))
      (node (ref "S9") (pin "1") (pinfunction "1_1") (pintype "passive"))
      (node (ref "VR3") (pin "P$1") (pinfunction "E_P$1") (pintype "passive"))
      (node (ref "VR3") (pin "P$2") (pinfunction "S_P$2") (pintype "passive"))
    )
    (net (code "49") (name "Net-(R4-P$2)") (class "Default")
      (node (ref "R4") (pin "2") (pinfunction "P$2_2") (pintype "bidirectional"))
      (node (ref "S9") (pin "3") (pinfunction "3_3") (pintype "passive"))
    )
    (net (code "50") (name "Net-(R5-P$1)") (class "Default")
      (node (ref "R5") (pin "1") (pinfunction "P$1_1") (pintype "bidirectional"))
      (node (ref "S12") (pin "1") (pinfunction "1_1") (pintype "passive"))
      (node (ref "VR4") (pin "P$1") (pinfunction "E_P$1") (pintype "passive"))
      (node (ref "VR4") (pin "P$2") (pinfunction "S_P$2") (pintype "passive"))
    )
    (net (code "51") (name "Net-(R5-P$2)") (class "Default")
      (node (ref "R5") (pin "2") (pinfunction "P$2_2") (pintype "bidirectional"))
      (node (ref "S12") (pin "3") (pinfunction "3_3") (pintype "passive"))
    )
    (net (code "52") (name "Net-(R6-2)") (class "Default")
      (node (ref "R6") (pin "P$2") (pinfunction "2_P$2") (pintype "passive"))
      (node (ref "VR1") (pin "P$3") (pinfunction "A_P$3") (pintype "passive"))
    )
    (net (code "53") (name "Net-(R7-2)") (class "Default")
      (node (ref "R7") (pin "P$2") (pinfunction "2_P$2") (pintype "passive"))
      (node (ref "VR2") (pin "P$3") (pinfunction "A_P$3") (pintype "passive"))
    )
    (net (code "54") (name "Net-(R8-2)") (class "Default")
      (node (ref "R8") (pin "P$2") (pinfunction "2_P$2") (pintype "passive"))
      (node (ref "VR3") (pin "P$3") (pinfunction "A_P$3") (pintype "passive"))
    )
    (net (code "55") (name "Net-(R9-2)") (class "Default")
      (node (ref "R9") (pin "P$2") (pinfunction "2_P$2") (pintype "passive"))
      (node (ref "VR4") (pin "P$3") (pinfunction "A_P$3") (pintype "passive"))
    )
    (net (code "56") (name "Net-(R10-2)") (class "Default")
      (node (ref "R10") (pin "P$2") (pinfunction "2_P$2") (pintype "passive"))
      (node (ref "VR5") (pin "P$3") (pinfunction "A_P$3") (pintype "passive"))
    )
    (net (code "57") (name "VCC") (class "Default")
      (node (ref "C12") (pin "1") (pinfunction "1_1") (pintype "passive"))
      (node (ref "C13") (pin "1") (pinfunction "1_1") (pintype "passive"))
      (node (ref "C9") (pin "1") (pinfunction "1_1") (pintype "passive"))
      (node (ref "IC1") (pin "14") (pinfunction "VDD_14") (pintype "power_in"))
      (node (ref "IC2") (pin "16") (pinfunction "VDD_16") (pintype "power_in"))
      (node (ref "IC3") (pin "14") (pinfunction "VDD_14") (pintype "power_in"))
      (node (ref "J1") (pin "4") (pinfunction "4_4") (pintype "passive"))
      (node (ref "J8") (pin "4") (pinfunction "4_4") (pintype "passive"))
      (node (ref "R1") (pin "P$2") (pinfunction "2_P$2") (pintype "passive"))
    )
    (net (code "58") (name "unconnected-(IC2A-DEMO-Pad10)") (class "Default")
      (node (ref "IC2") (pin "10") (pinfunction "DEMO_10") (pintype "output"))
    )
    (net (code "59") (name "unconnected-(IC2A-PC2-Pad13)") (class "Default")
      (node (ref "IC2") (pin "13") (pinfunction "PC2_13") (pintype "output"))
    )
    (net (code "60") (name "unconnected-(IC2A-PP-Pad1)") (class "Default")
      (node (ref "IC2") (pin "1") (pinfunction "PP_1") (pintype "output"))
    )
    (net (code "61") (name "unconnected-(IC2A-R2-Pad12)") (class "Default")
      (node (ref "IC2") (pin "12") (pinfunction "R2_12") (pintype "input"))
    )
    (net (code "62") (name "unconnected-(IC2A-ZEN-Pad15)") (class "Default")
      (node (ref "IC2") (pin "15") (pinfunction "ZEN_15") (pintype "input"))
    )
  )
)
